# pycubed.net
KiCad netlist of a schematic drawn in EAGLE
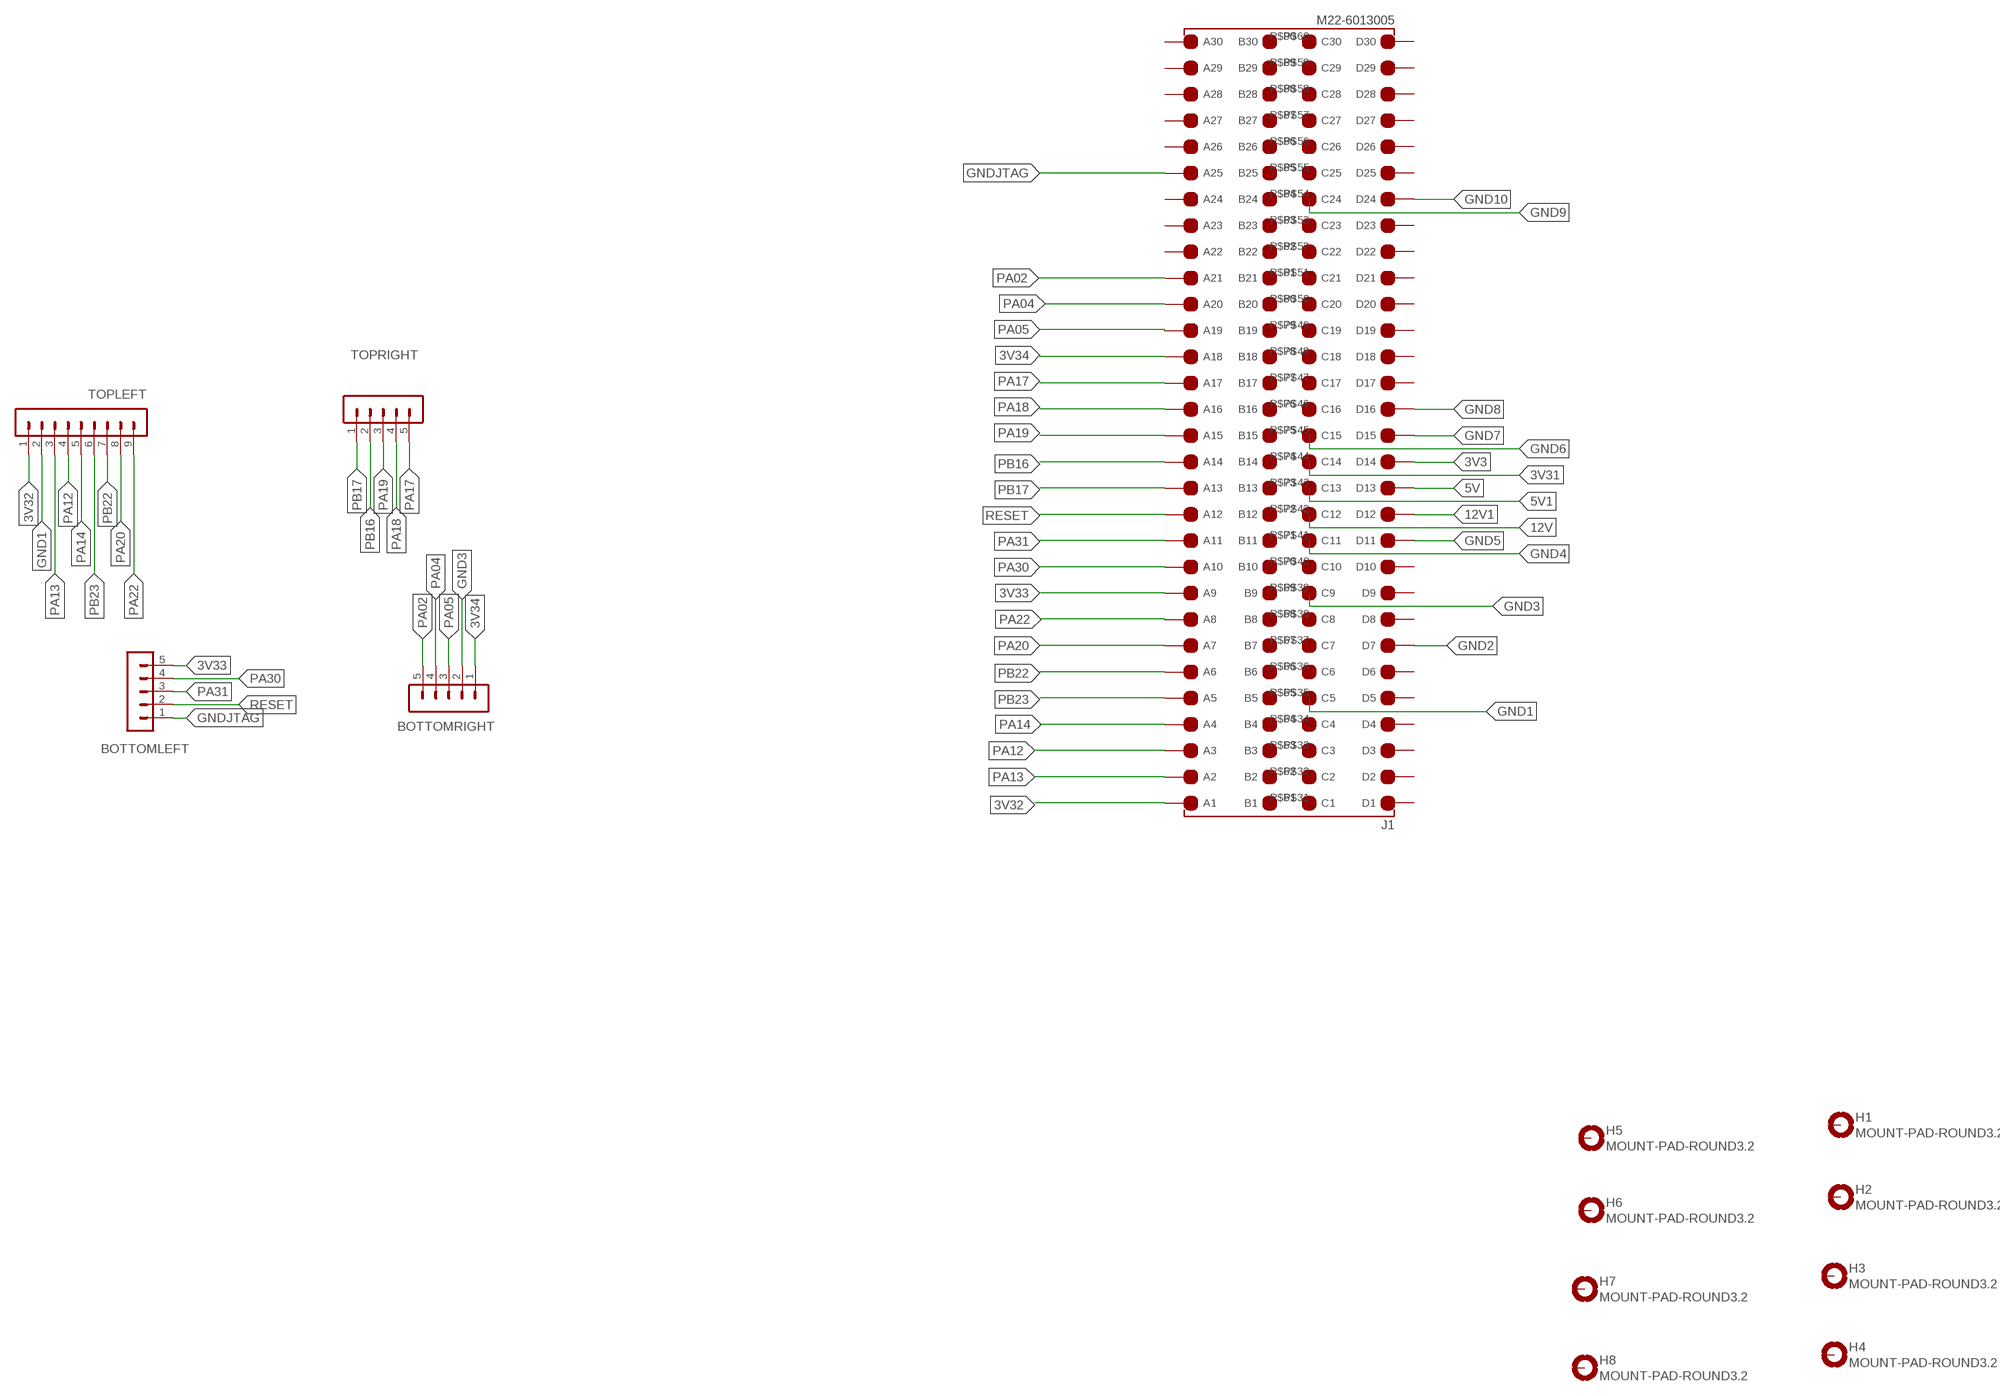
[diagram p0: schematic, sheet 1]

(export (version "E")
  (design (tool "Eeschema 10.0.6"))
  (components
    (comp (ref "BOTTOMLEFT")
      (value "MA05-1")
      (footprint "eagle-import:MA05-1")
      (libsource (lib "eagle-import") (part "MA05-1"))
    )
    (comp (ref "BOTTOMRIGHT")
      (value "MA05-1")
      (footprint "eagle-import:MA05-1")
      (libsource (lib "eagle-import") (part "MA05-1"))
    )
    (comp (ref "H1")
      (value "MOUNT-PAD-ROUND3.2")
      (footprint "eagle-import:3,2-PAD")
      (libsource (lib "eagle-import") (part "MOUNT-PAD-ROUND3.2"))
    )
    (comp (ref "H2")
      (value "MOUNT-PAD-ROUND3.2")
      (footprint "eagle-import:3,2-PAD")
      (libsource (lib "eagle-import") (part "MOUNT-PAD-ROUND3.2"))
    )
    (comp (ref "H3")
      (value "MOUNT-PAD-ROUND3.2")
      (footprint "eagle-import:3,2-PAD")
      (libsource (lib "eagle-import") (part "MOUNT-PAD-ROUND3.2"))
    )
    (comp (ref "H4")
      (value "MOUNT-PAD-ROUND3.2")
      (footprint "eagle-import:3,2-PAD")
      (libsource (lib "eagle-import") (part "MOUNT-PAD-ROUND3.2"))
    )
    (comp (ref "H5")
      (value "MOUNT-PAD-ROUND3.2")
      (footprint "eagle-import:3,2-PAD")
      (libsource (lib "eagle-import") (part "MOUNT-PAD-ROUND3.2"))
    )
    (comp (ref "H6")
      (value "MOUNT-PAD-ROUND3.2")
      (footprint "eagle-import:3,2-PAD")
      (libsource (lib "eagle-import") (part "MOUNT-PAD-ROUND3.2"))
    )
    (comp (ref "H7")
      (value "MOUNT-PAD-ROUND3.2")
      (footprint "eagle-import:3,2-PAD")
      (libsource (lib "eagle-import") (part "MOUNT-PAD-ROUND3.2"))
    )
    (comp (ref "H8")
      (value "MOUNT-PAD-ROUND3.2")
      (footprint "eagle-import:3,2-PAD")
      (libsource (lib "eagle-import") (part "MOUNT-PAD-ROUND3.2"))
    )
    (comp (ref "J1")
      (value "M22-6013005")
      (footprint "eagle-import:RHDR120W55P200_4X30_6020X820X9")
      (libsource (lib "eagle-import") (part "M22-6013005"))
    )
    (comp (ref "TOPLEFT")
      (value "MA09-1")
      (footprint "eagle-import:MA09-1")
      (libsource (lib "eagle-import") (part "MA09-1"))
    )
    (comp (ref "TOPRIGHT")
      (value "MA05-1")
      (footprint "eagle-import:MA05-1")
      (libsource (lib "eagle-import") (part "MA05-1"))
    )
  )
  (nets
    (net (code "1") (name "3V3") (class "Default")
      (node (ref "J1") (pin "P$14") (pinfunction "D14_P$14") (pintype "passive"))
    )
    (net (code "2") (name "3V31") (class "Default")
      (node (ref "J1") (pin "P$44") (pinfunction "C14_P$44") (pintype "passive"))
    )
    (net (code "3") (name "3V32") (class "Default")
      (node (ref "J1") (pin "P$91") (pinfunction "A1_P$91") (pintype "passive"))
      (node (ref "TOPLEFT") (pin "1") (pinfunction "1_1") (pintype "passive"))
    )
    (net (code "4") (name "3V33") (class "Default")
      (node (ref "BOTTOMLEFT") (pin "5") (pinfunction "5_5") (pintype "passive"))
      (node (ref "J1") (pin "P$99") (pinfunction "A9_P$99") (pintype "passive"))
    )
    (net (code "5") (name "3V34") (class "Default")
      (node (ref "BOTTOMRIGHT") (pin "1") (pinfunction "1_1") (pintype "passive"))
      (node (ref "J1") (pin "P$108") (pinfunction "A18_P$108") (pintype "passive"))
    )
    (net (code "6") (name "5V") (class "Default")
      (node (ref "J1") (pin "P$13") (pinfunction "D13_P$13") (pintype "passive"))
    )
    (net (code "7") (name "5V1") (class "Default")
      (node (ref "J1") (pin "P$43") (pinfunction "C13_P$43") (pintype "passive"))
    )
    (net (code "8") (name "12V") (class "Default")
      (node (ref "J1") (pin "P$42") (pinfunction "C12_P$42") (pintype "passive"))
    )
    (net (code "9") (name "12V1") (class "Default")
      (node (ref "J1") (pin "P$12") (pinfunction "D12_P$12") (pintype "passive"))
    )
    (net (code "10") (name "GND1") (class "Default")
      (node (ref "J1") (pin "P$35") (pinfunction "C5_P$35") (pintype "passive"))
      (node (ref "TOPLEFT") (pin "2") (pinfunction "2_2") (pintype "passive"))
    )
    (net (code "11") (name "GND2") (class "Default")
      (node (ref "J1") (pin "P$7") (pinfunction "D7_P$7") (pintype "passive"))
    )
    (net (code "12") (name "GND3") (class "Default")
      (node (ref "BOTTOMRIGHT") (pin "2") (pinfunction "2_2") (pintype "passive"))
      (node (ref "J1") (pin "P$39") (pinfunction "C9_P$39") (pintype "passive"))
    )
    (net (code "13") (name "GND4") (class "Default")
      (node (ref "J1") (pin "P$41") (pinfunction "C11_P$41") (pintype "passive"))
    )
    (net (code "14") (name "GND5") (class "Default")
      (node (ref "J1") (pin "P$11") (pinfunction "D11_P$11") (pintype "passive"))
    )
    (net (code "15") (name "GND6") (class "Default")
      (node (ref "J1") (pin "P$45") (pinfunction "C15_P$45") (pintype "passive"))
    )
    (net (code "16") (name "GND7") (class "Default")
      (node (ref "J1") (pin "P$15") (pinfunction "D15_P$15") (pintype "passive"))
    )
    (net (code "17") (name "GND8") (class "Default")
      (node (ref "J1") (pin "P$16") (pinfunction "D16_P$16") (pintype "passive"))
    )
    (net (code "18") (name "GND9") (class "Default")
      (node (ref "J1") (pin "P$54") (pinfunction "C24_P$54") (pintype "passive"))
    )
    (net (code "19") (name "GND10") (class "Default")
      (node (ref "J1") (pin "P$24") (pinfunction "D24_P$24") (pintype "passive"))
    )
    (net (code "20") (name "GNDJTAG") (class "Default")
      (node (ref "BOTTOMLEFT") (pin "1") (pinfunction "1_1") (pintype "passive"))
      (node (ref "J1") (pin "P$115") (pinfunction "A25_P$115") (pintype "passive"))
    )
    (net (code "21") (name "PA02") (class "Default")
      (node (ref "BOTTOMRIGHT") (pin "5") (pinfunction "5_5") (pintype "passive"))
      (node (ref "J1") (pin "P$111") (pinfunction "A21_P$111") (pintype "passive"))
    )
    (net (code "22") (name "PA04") (class "Default")
      (node (ref "BOTTOMRIGHT") (pin "4") (pinfunction "4_4") (pintype "passive"))
      (node (ref "J1") (pin "P$110") (pinfunction "A20_P$110") (pintype "passive"))
    )
    (net (code "23") (name "PA05") (class "Default")
      (node (ref "BOTTOMRIGHT") (pin "3") (pinfunction "3_3") (pintype "passive"))
      (node (ref "J1") (pin "P$109") (pinfunction "A19_P$109") (pintype "passive"))
    )
    (net (code "24") (name "PA12") (class "Default")
      (node (ref "J1") (pin "P$93") (pinfunction "A3_P$93") (pintype "passive"))
      (node (ref "TOPLEFT") (pin "4") (pinfunction "4_4") (pintype "passive"))
    )
    (net (code "25") (name "PA13") (class "Default")
      (node (ref "J1") (pin "P$92") (pinfunction "A2_P$92") (pintype "passive"))
      (node (ref "TOPLEFT") (pin "3") (pinfunction "3_3") (pintype "passive"))
    )
    (net (code "26") (name "PA14") (class "Default")
      (node (ref "J1") (pin "P$94") (pinfunction "A4_P$94") (pintype "passive"))
      (node (ref "TOPLEFT") (pin "5") (pinfunction "5_5") (pintype "passive"))
    )
    (net (code "27") (name "PA17") (class "Default")
      (node (ref "J1") (pin "P$107") (pinfunction "A17_P$107") (pintype "passive"))
      (node (ref "TOPRIGHT") (pin "5") (pinfunction "5_5") (pintype "passive"))
    )
    (net (code "28") (name "PA18") (class "Default")
      (node (ref "J1") (pin "P$106") (pinfunction "A16_P$106") (pintype "passive"))
      (node (ref "TOPRIGHT") (pin "4") (pinfunction "4_4") (pintype "passive"))
    )
    (net (code "29") (name "PA19") (class "Default")
      (node (ref "J1") (pin "P$105") (pinfunction "A15_P$105") (pintype "passive"))
      (node (ref "TOPRIGHT") (pin "3") (pinfunction "3_3") (pintype "passive"))
    )
    (net (code "30") (name "PA20") (class "Default")
      (node (ref "J1") (pin "P$97") (pinfunction "A7_P$97") (pintype "passive"))
      (node (ref "TOPLEFT") (pin "8") (pinfunction "8_8") (pintype "passive"))
    )
    (net (code "31") (name "PA22") (class "Default")
      (node (ref "J1") (pin "P$98") (pinfunction "A8_P$98") (pintype "passive"))
      (node (ref "TOPLEFT") (pin "9") (pinfunction "9_9") (pintype "passive"))
    )
    (net (code "32") (name "PA30") (class "Default")
      (node (ref "BOTTOMLEFT") (pin "4") (pinfunction "4_4") (pintype "passive"))
      (node (ref "J1") (pin "P$100") (pinfunction "A10_P$100") (pintype "passive"))
    )
    (net (code "33") (name "PA31") (class "Default")
      (node (ref "BOTTOMLEFT") (pin "3") (pinfunction "3_3") (pintype "passive"))
      (node (ref "J1") (pin "P$101") (pinfunction "A11_P$101") (pintype "passive"))
    )
    (net (code "34") (name "PB16") (class "Default")
      (node (ref "J1") (pin "P$104") (pinfunction "A14_P$104") (pintype "passive"))
      (node (ref "TOPRIGHT") (pin "2") (pinfunction "2_2") (pintype "passive"))
    )
    (net (code "35") (name "PB17") (class "Default")
      (node (ref "J1") (pin "P$103") (pinfunction "A13_P$103") (pintype "passive"))
      (node (ref "TOPRIGHT") (pin "1") (pinfunction "1_1") (pintype "passive"))
    )
    (net (code "36") (name "PB22") (class "Default")
      (node (ref "J1") (pin "P$96") (pinfunction "A6_P$96") (pintype "passive"))
      (node (ref "TOPLEFT") (pin "7") (pinfunction "7_7") (pintype "passive"))
    )
    (net (code "37") (name "PB23") (class "Default")
      (node (ref "J1") (pin "P$95") (pinfunction "A5_P$95") (pintype "passive"))
      (node (ref "TOPLEFT") (pin "6") (pinfunction "6_6") (pintype "passive"))
    )
    (net (code "38") (name "RESET") (class "Default")
      (node (ref "BOTTOMLEFT") (pin "2") (pinfunction "2_2") (pintype "passive"))
      (node (ref "J1") (pin "P$102") (pinfunction "A12_P$102") (pintype "passive"))
    )
    (net (code "39") (name "unconnected-(H1-MOUNT-PadB3,2)") (class "Default")
      (node (ref "H1") (pin "B3,2") (pinfunction "MOUNT_B3,2") (pintype "passive"))
    )
    (net (code "40") (name "unconnected-(H2-MOUNT-PadB3,2)") (class "Default")
      (node (ref "H2") (pin "B3,2") (pinfunction "MOUNT_B3,2") (pintype "passive"))
    )
    (net (code "41") (name "unconnected-(H3-MOUNT-PadB3,2)") (class "Default")
      (node (ref "H3") (pin "B3,2") (pinfunction "MOUNT_B3,2") (pintype "passive"))
    )
    (net (code "42") (name "unconnected-(H4-MOUNT-PadB3,2)") (class "Default")
      (node (ref "H4") (pin "B3,2") (pinfunction "MOUNT_B3,2") (pintype "passive"))
    )
    (net (code "43") (name "unconnected-(H5-MOUNT-PadB3,2)") (class "Default")
      (node (ref "H5") (pin "B3,2") (pinfunction "MOUNT_B3,2") (pintype "passive"))
    )
    (net (code "44") (name "unconnected-(H6-MOUNT-PadB3,2)") (class "Default")
      (node (ref "H6") (pin "B3,2") (pinfunction "MOUNT_B3,2") (pintype "passive"))
    )
    (net (code "45") (name "unconnected-(H7-MOUNT-PadB3,2)") (class "Default")
      (node (ref "H7") (pin "B3,2") (pinfunction "MOUNT_B3,2") (pintype "passive"))
    )
    (net (code "46") (name "unconnected-(H8-MOUNT-PadB3,2)") (class "Default")
      (node (ref "H8") (pin "B3,2") (pinfunction "MOUNT_B3,2") (pintype "passive"))
    )
    (net (code "47") (name "unconnected-(J1-A22-PadP$112)") (class "Default")
      (node (ref "J1") (pin "P$112") (pinfunction "A22_P$112") (pintype "passive"))
    )
    (net (code "48") (name "unconnected-(J1-A23-PadP$113)") (class "Default")
      (node (ref "J1") (pin "P$113") (pinfunction "A23_P$113") (pintype "passive"))
    )
    (net (code "49") (name "unconnected-(J1-A24-PadP$114)") (class "Default")
      (node (ref "J1") (pin "P$114") (pinfunction "A24_P$114") (pintype "passive"))
    )
    (net (code "50") (name "unconnected-(J1-A26-PadP$116)") (class "Default")
      (node (ref "J1") (pin "P$116") (pinfunction "A26_P$116") (pintype "passive"))
    )
    (net (code "51") (name "unconnected-(J1-A27-PadP$117)") (class "Default")
      (node (ref "J1") (pin "P$117") (pinfunction "A27_P$117") (pintype "passive"))
    )
    (net (code "52") (name "unconnected-(J1-A28-PadP$118)") (class "Default")
      (node (ref "J1") (pin "P$118") (pinfunction "A28_P$118") (pintype "passive"))
    )
    (net (code "53") (name "unconnected-(J1-A29-PadP$119)") (class "Default")
      (node (ref "J1") (pin "P$119") (pinfunction "A29_P$119") (pintype "passive"))
    )
    (net (code "54") (name "unconnected-(J1-A30-PadP$120)") (class "Default")
      (node (ref "J1") (pin "P$120") (pinfunction "A30_P$120") (pintype "passive"))
    )
    (net (code "55") (name "unconnected-(J1-B1-PadP$61)") (class "Default")
      (node (ref "J1") (pin "P$61") (pinfunction "B1_P$61") (pintype "passive"))
    )
    (net (code "56") (name "unconnected-(J1-B2-PadP$62)") (class "Default")
      (node (ref "J1") (pin "P$62") (pinfunction "B2_P$62") (pintype "passive"))
    )
    (net (code "57") (name "unconnected-(J1-B3-PadP$63)") (class "Default")
      (node (ref "J1") (pin "P$63") (pinfunction "B3_P$63") (pintype "passive"))
    )
    (net (code "58") (name "unconnected-(J1-B4-PadP$64)") (class "Default")
      (node (ref "J1") (pin "P$64") (pinfunction "B4_P$64") (pintype "passive"))
    )
    (net (code "59") (name "unconnected-(J1-B5-PadP$65)") (class "Default")
      (node (ref "J1") (pin "P$65") (pinfunction "B5_P$65") (pintype "passive"))
    )
    (net (code "60") (name "unconnected-(J1-B6-PadP$66)") (class "Default")
      (node (ref "J1") (pin "P$66") (pinfunction "B6_P$66") (pintype "passive"))
    )
    (net (code "61") (name "unconnected-(J1-B7-PadP$67)") (class "Default")
      (node (ref "J1") (pin "P$67") (pinfunction "B7_P$67") (pintype "passive"))
    )
    (net (code "62") (name "unconnected-(J1-B8-PadP$68)") (class "Default")
      (node (ref "J1") (pin "P$68") (pinfunction "B8_P$68") (pintype "passive"))
    )
    (net (code "63") (name "unconnected-(J1-B9-PadP$69)") (class "Default")
      (node (ref "J1") (pin "P$69") (pinfunction "B9_P$69") (pintype "passive"))
    )
    (net (code "64") (name "unconnected-(J1-B10-PadP$70)") (class "Default")
      (node (ref "J1") (pin "P$70") (pinfunction "B10_P$70") (pintype "passive"))
    )
    (net (code "65") (name "unconnected-(J1-B11-PadP$71)") (class "Default")
      (node (ref "J1") (pin "P$71") (pinfunction "B11_P$71") (pintype "passive"))
    )
    (net (code "66") (name "unconnected-(J1-B12-PadP$72)") (class "Default")
      (node (ref "J1") (pin "P$72") (pinfunction "B12_P$72") (pintype "passive"))
    )
    (net (code "67") (name "unconnected-(J1-B13-PadP$73)") (class "Default")
      (node (ref "J1") (pin "P$73") (pinfunction "B13_P$73") (pintype "passive"))
    )
    (net (code "68") (name "unconnected-(J1-B14-PadP$74)") (class "Default")
      (node (ref "J1") (pin "P$74") (pinfunction "B14_P$74") (pintype "passive"))
    )
    (net (code "69") (name "unconnected-(J1-B15-PadP$75)") (class "Default")
      (node (ref "J1") (pin "P$75") (pinfunction "B15_P$75") (pintype "passive"))
    )
    (net (code "70") (name "unconnected-(J1-B16-PadP$76)") (class "Default")
      (node (ref "J1") (pin "P$76") (pinfunction "B16_P$76") (pintype "passive"))
    )
    (net (code "71") (name "unconnected-(J1-B17-PadP$77)") (class "Default")
      (node (ref "J1") (pin "P$77") (pinfunction "B17_P$77") (pintype "passive"))
    )
    (net (code "72") (name "unconnected-(J1-B18-PadP$78)") (class "Default")
      (node (ref "J1") (pin "P$78") (pinfunction "B18_P$78") (pintype "passive"))
    )
    (net (code "73") (name "unconnected-(J1-B19-PadP$79)") (class "Default")
      (node (ref "J1") (pin "P$79") (pinfunction "B19_P$79") (pintype "passive"))
    )
    (net (code "74") (name "unconnected-(J1-B20-PadP$80)") (class "Default")
      (node (ref "J1") (pin "P$80") (pinfunction "B20_P$80") (pintype "passive"))
    )
    (net (code "75") (name "unconnected-(J1-B21-PadP$81)") (class "Default")
      (node (ref "J1") (pin "P$81") (pinfunction "B21_P$81") (pintype "passive"))
    )
    (net (code "76") (name "unconnected-(J1-B22-PadP$82)") (class "Default")
      (node (ref "J1") (pin "P$82") (pinfunction "B22_P$82") (pintype "passive"))
    )
    (net (code "77") (name "unconnected-(J1-B23-PadP$83)") (class "Default")
      (node (ref "J1") (pin "P$83") (pinfunction "B23_P$83") (pintype "passive"))
    )
    (net (code "78") (name "unconnected-(J1-B24-PadP$84)") (class "Default")
      (node (ref "J1") (pin "P$84") (pinfunction "B24_P$84") (pintype "passive"))
    )
    (net (code "79") (name "unconnected-(J1-B25-PadP$85)") (class "Default")
      (node (ref "J1") (pin "P$85") (pinfunction "B25_P$85") (pintype "passive"))
    )
    (net (code "80") (name "unconnected-(J1-B26-PadP$86)") (class "Default")
      (node (ref "J1") (pin "P$86") (pinfunction "B26_P$86") (pintype "passive"))
    )
    (net (code "81") (name "unconnected-(J1-B27-PadP$87)") (class "Default")
      (node (ref "J1") (pin "P$87") (pinfunction "B27_P$87") (pintype "passive"))
    )
    (net (code "82") (name "unconnected-(J1-B28-PadP$88)") (class "Default")
      (node (ref "J1") (pin "P$88") (pinfunction "B28_P$88") (pintype "passive"))
    )
    (net (code "83") (name "unconnected-(J1-B29-PadP$89)") (class "Default")
      (node (ref "J1") (pin "P$89") (pinfunction "B29_P$89") (pintype "passive"))
    )
    (net (code "84") (name "unconnected-(J1-B30-PadP$90)") (class "Default")
      (node (ref "J1") (pin "P$90") (pinfunction "B30_P$90") (pintype "passive"))
    )
    (net (code "85") (name "unconnected-(J1-C1-PadP$31)") (class "Default")
      (node (ref "J1") (pin "P$31") (pinfunction "C1_P$31") (pintype "passive"))
    )
    (net (code "86") (name "unconnected-(J1-C2-PadP$32)") (class "Default")
      (node (ref "J1") (pin "P$32") (pinfunction "C2_P$32") (pintype "passive"))
    )
    (net (code "87") (name "unconnected-(J1-C3-PadP$33)") (class "Default")
      (node (ref "J1") (pin "P$33") (pinfunction "C3_P$33") (pintype "passive"))
    )
    (net (code "88") (name "unconnected-(J1-C4-PadP$34)") (class "Default")
      (node (ref "J1") (pin "P$34") (pinfunction "C4_P$34") (pintype "passive"))
    )
    (net (code "89") (name "unconnected-(J1-C6-PadP$36)") (class "Default")
      (node (ref "J1") (pin "P$36") (pinfunction "C6_P$36") (pintype "passive"))
    )
    (net (code "90") (name "unconnected-(J1-C7-PadP$37)") (class "Default")
      (node (ref "J1") (pin "P$37") (pinfunction "C7_P$37") (pintype "passive"))
    )
    (net (code "91") (name "unconnected-(J1-C8-PadP$38)") (class "Default")
      (node (ref "J1") (pin "P$38") (pinfunction "C8_P$38") (pintype "passive"))
    )
    (net (code "92") (name "unconnected-(J1-C10-PadP$40)") (class "Default")
      (node (ref "J1") (pin "P$40") (pinfunction "C10_P$40") (pintype "passive"))
    )
    (net (code "93") (name "unconnected-(J1-C16-PadP$46)") (class "Default")
      (node (ref "J1") (pin "P$46") (pinfunction "C16_P$46") (pintype "passive"))
    )
    (net (code "94") (name "unconnected-(J1-C17-PadP$47)") (class "Default")
      (node (ref "J1") (pin "P$47") (pinfunction "C17_P$47") (pintype "passive"))
    )
    (net (code "95") (name "unconnected-(J1-C18-PadP$48)") (class "Default")
      (node (ref "J1") (pin "P$48") (pinfunction "C18_P$48") (pintype "passive"))
    )
    (net (code "96") (name "unconnected-(J1-C19-PadP$49)") (class "Default")
      (node (ref "J1") (pin "P$49") (pinfunction "C19_P$49") (pintype "passive"))
    )
    (net (code "97") (name "unconnected-(J1-C20-PadP$50)") (class "Default")
      (node (ref "J1") (pin "P$50") (pinfunction "C20_P$50") (pintype "passive"))
    )
    (net (code "98") (name "unconnected-(J1-C21-PadP$51)") (class "Default")
      (node (ref "J1") (pin "P$51") (pinfunction "C21_P$51") (pintype "passive"))
    )
    (net (code "99") (name "unconnected-(J1-C22-PadP$52)") (class "Default")
      (node (ref "J1") (pin "P$52") (pinfunction "C22_P$52") (pintype "passive"))
    )
    (net (code "100") (name "unconnected-(J1-C23-PadP$53)") (class "Default")
      (node (ref "J1") (pin "P$53") (pinfunction "C23_P$53") (pintype "passive"))
    )
    (net (code "101") (name "unconnected-(J1-C25-PadP$55)") (class "Default")
      (node (ref "J1") (pin "P$55") (pinfunction "C25_P$55") (pintype "passive"))
    )
    (net (code "102") (name "unconnected-(J1-C26-PadP$56)") (class "Default")
      (node (ref "J1") (pin "P$56") (pinfunction "C26_P$56") (pintype "passive"))
    )
    (net (code "103") (name "unconnected-(J1-C27-PadP$57)") (class "Default")
      (node (ref "J1") (pin "P$57") (pinfunction "C27_P$57") (pintype "passive"))
    )
    (net (code "104") (name "unconnected-(J1-C28-PadP$58)") (class "Default")
      (node (ref "J1") (pin "P$58") (pinfunction "C28_P$58") (pintype "passive"))
    )
    (net (code "105") (name "unconnected-(J1-C29-PadP$59)") (class "Default")
      (node (ref "J1") (pin "P$59") (pinfunction "C29_P$59") (pintype "passive"))
    )
    (net (code "106") (name "unconnected-(J1-C30-PadP$60)") (class "Default")
      (node (ref "J1") (pin "P$60") (pinfunction "C30_P$60") (pintype "passive"))
    )
    (net (code "107") (name "unconnected-(J1-D1-PadP$1)") (class "Default")
      (node (ref "J1") (pin "P$1") (pinfunction "D1_P$1") (pintype "passive"))
    )
    (net (code "108") (name "unconnected-(J1-D2-PadP$2)") (class "Default")
      (node (ref "J1") (pin "P$2") (pinfunction "D2_P$2") (pintype "passive"))
    )
    (net (code "109") (name "unconnected-(J1-D3-PadP$3)") (class "Default")
      (node (ref "J1") (pin "P$3") (pinfunction "D3_P$3") (pintype "passive"))
    )
    (net (code "110") (name "unconnected-(J1-D4-PadP$4)") (class "Default")
      (node (ref "J1") (pin "P$4") (pinfunction "D4_P$4") (pintype "passive"))
    )
    (net (code "111") (name "unconnected-(J1-D5-PadP$5)") (class "Default")
      (node (ref "J1") (pin "P$5") (pinfunction "D5_P$5") (pintype "passive"))
    )
    (net (code "112") (name "unconnected-(J1-D6-PadP$6)") (class "Default")
      (node (ref "J1") (pin "P$6") (pinfunction "D6_P$6") (pintype "passive"))
    )
    (net (code "113") (name "unconnected-(J1-D8-PadP$8)") (class "Default")
      (node (ref "J1") (pin "P$8") (pinfunction "D8_P$8") (pintype "passive"))
    )
    (net (code "114") (name "unconnected-(J1-D9-PadP$9)") (class "Default")
      (node (ref "J1") (pin "P$9") (pinfunction "D9_P$9") (pintype "passive"))
    )
    (net (code "115") (name "unconnected-(J1-D10-PadP$10)") (class "Default")
      (node (ref "J1") (pin "P$10") (pinfunction "D10_P$10") (pintype "passive"))
    )
    (net (code "116") (name "unconnected-(J1-D17-PadP$17)") (class "Default")
      (node (ref "J1") (pin "P$17") (pinfunction "D17_P$17") (pintype "passive"))
    )
    (net (code "117") (name "unconnected-(J1-D18-PadP$18)") (class "Default")
      (node (ref "J1") (pin "P$18") (pinfunction "D18_P$18") (pintype "passive"))
    )
    (net (code "118") (name "unconnected-(J1-D19-PadP$19)") (class "Default")
      (node (ref "J1") (pin "P$19") (pinfunction "D19_P$19") (pintype "passive"))
    )
    (net (code "119") (name "unconnected-(J1-D20-PadP$20)") (class "Default")
      (node (ref "J1") (pin "P$20") (pinfunction "D20_P$20") (pintype "passive"))
    )
    (net (code "120") (name "unconnected-(J1-D21-PadP$21)") (class "Default")
      (node (ref "J1") (pin "P$21") (pinfunction "D21_P$21") (pintype "passive"))
    )
    (net (code "121") (name "unconnected-(J1-D22-PadP$22)") (class "Default")
      (node (ref "J1") (pin "P$22") (pinfunction "D22_P$22") (pintype "passive"))
    )
    (net (code "122") (name "unconnected-(J1-D23-PadP$23)") (class "Default")
      (node (ref "J1") (pin "P$23") (pinfunction "D23_P$23") (pintype "passive"))
    )
    (net (code "123") (name "unconnected-(J1-D25-PadP$25)") (class "Default")
      (node (ref "J1") (pin "P$25") (pinfunction "D25_P$25") (pintype "passive"))
    )
    (net (code "124") (name "unconnected-(J1-D26-PadP$26)") (class "Default")
      (node (ref "J1") (pin "P$26") (pinfunction "D26_P$26") (pintype "passive"))
    )
    (net (code "125") (name "unconnected-(J1-D27-PadP$27)") (class "Default")
      (node (ref "J1") (pin "P$27") (pinfunction "D27_P$27") (pintype "passive"))
    )
    (net (code "126") (name "unconnected-(J1-D28-PadP$28)") (class "Default")
      (node (ref "J1") (pin "P$28") (pinfunction "D28_P$28") (pintype "passive"))
    )
    (net (code "127") (name "unconnected-(J1-D29-PadP$29)") (class "Default")
      (node (ref "J1") (pin "P$29") (pinfunction "D29_P$29") (pintype "passive"))
    )
    (net (code "128") (name "unconnected-(J1-D30-PadP$30)") (class "Default")
      (node (ref "J1") (pin "P$30") (pinfunction "D30_P$30") (pintype "passive"))
    )
  )
)
